# BattleBits_V3_partlyRouted.net
KiCad netlist of a schematic drawn in EAGLE
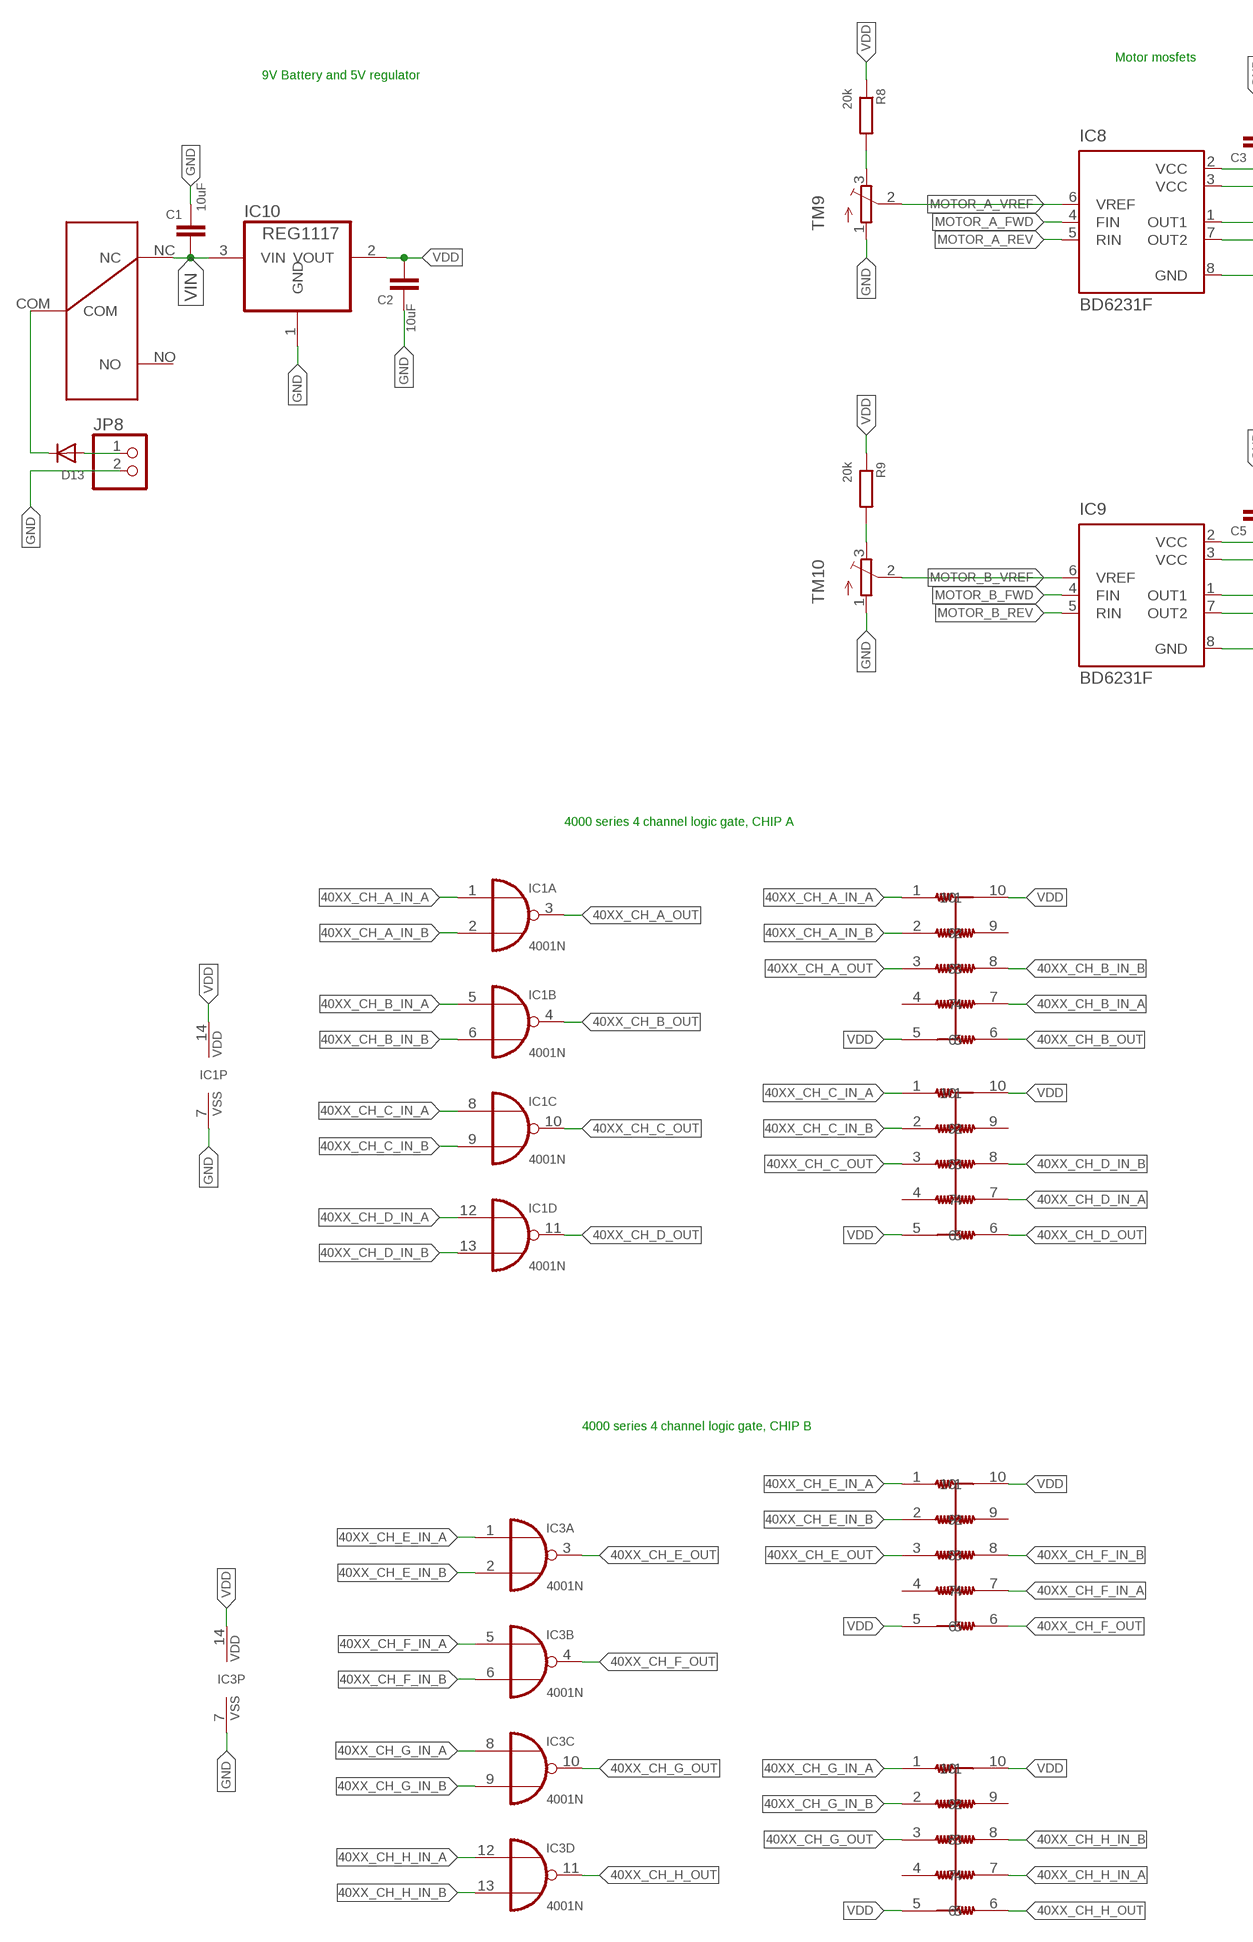
[diagram p0: schematic, sheet 1, part 1 of 2]
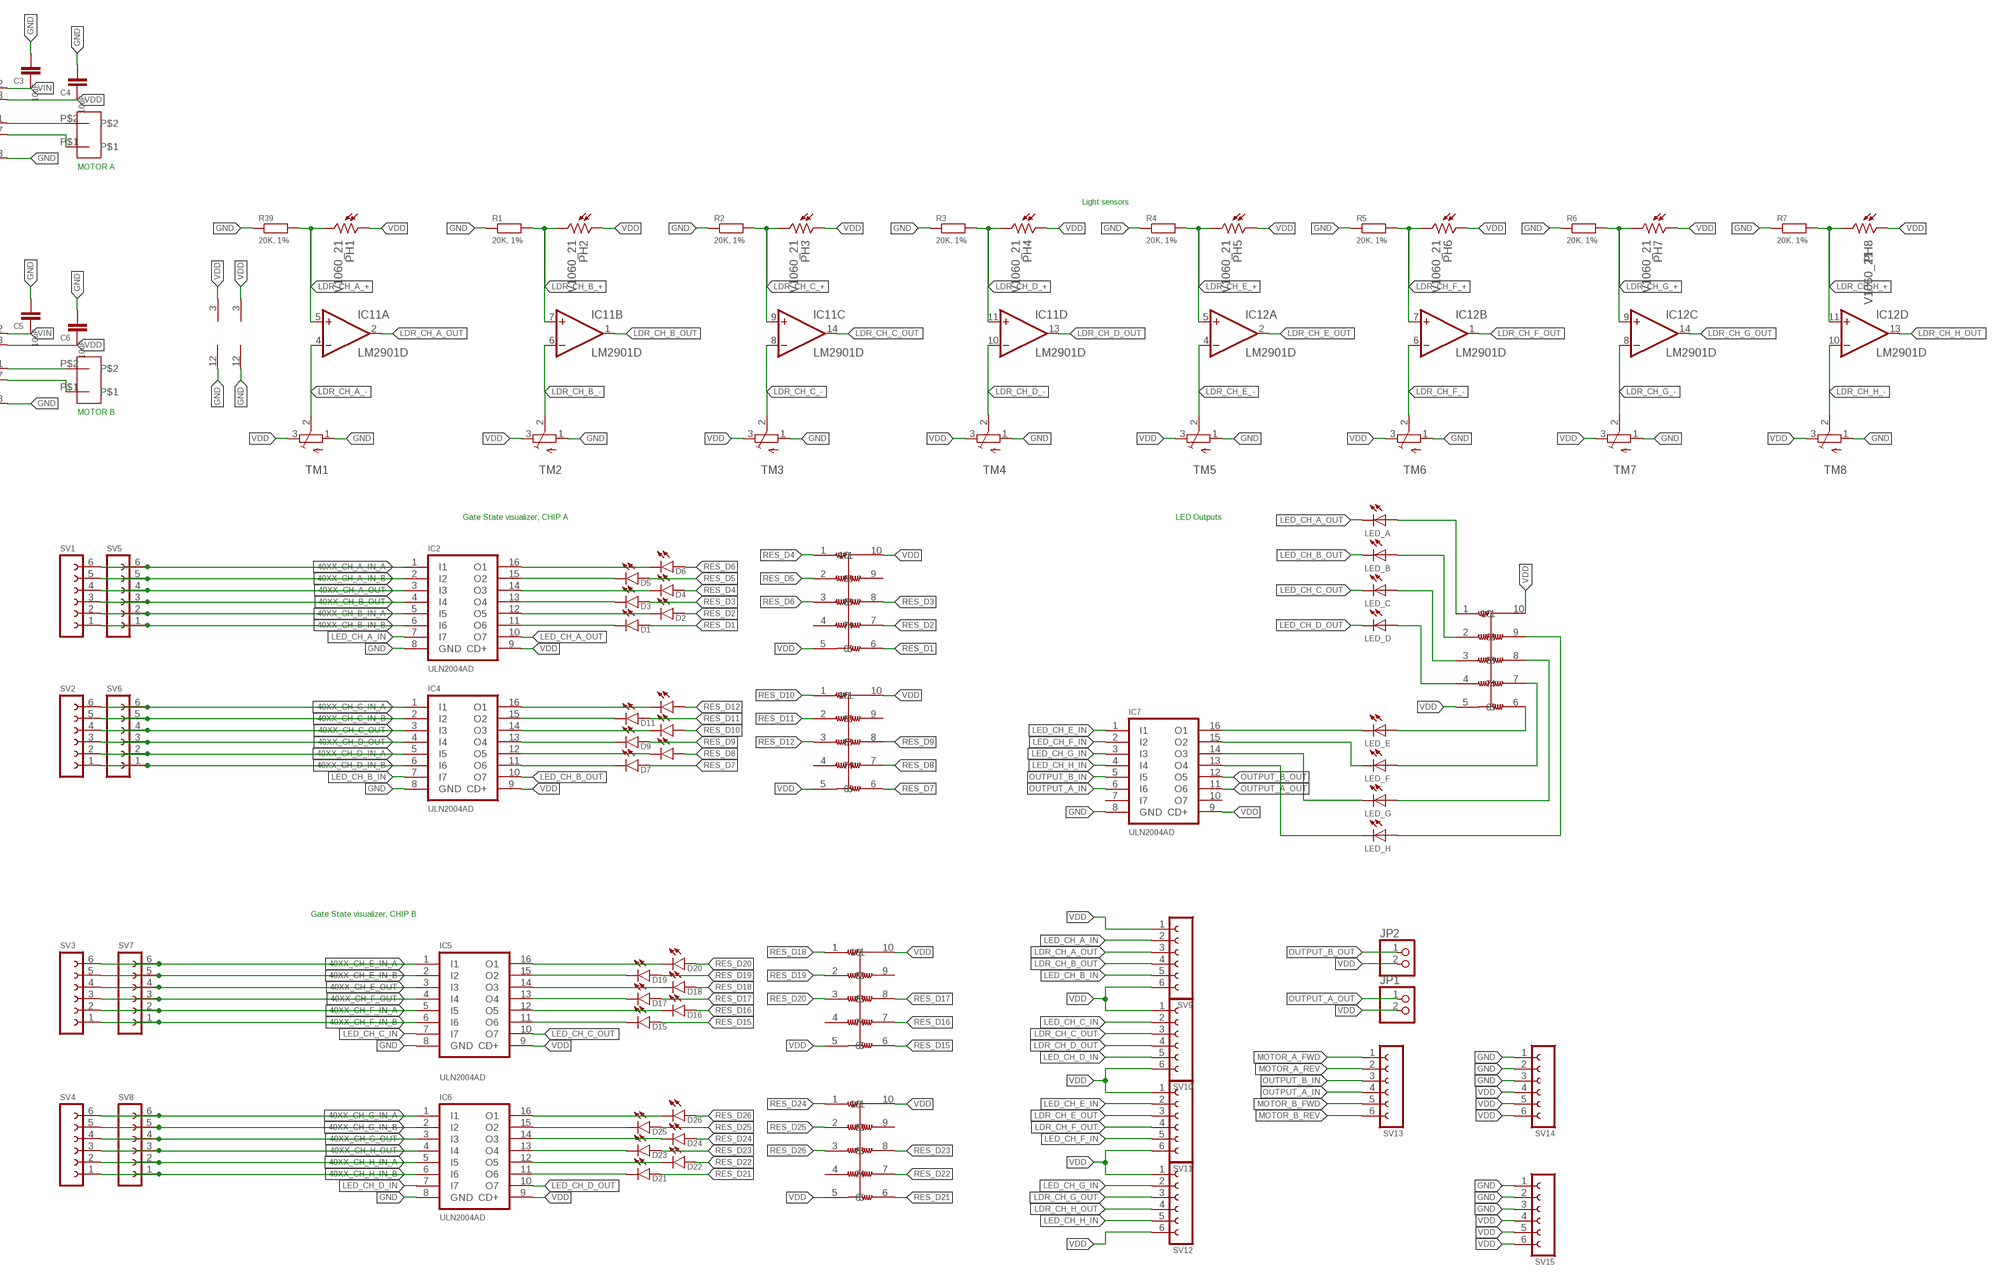
[diagram p1: schematic, sheet 1, part 2 of 2]

(export (version "E")
  (design (tool "Eeschema 10.0.6"))
  (components
    (comp (ref "C1")
      (value "10uF")
      (footprint "eagle-import:C3216")
      (libsource (lib "eagle-import") (part "C-EUC3216"))
    )
    (comp (ref "C2")
      (value "10uF")
      (footprint "eagle-import:C3216")
      (libsource (lib "eagle-import") (part "C-EUC3216"))
    )
    (comp (ref "C3")
      (value "10uF")
      (footprint "eagle-import:C3216")
      (libsource (lib "eagle-import") (part "C-EUC3216"))
    )
    (comp (ref "C4")
      (value "10uF")
      (footprint "eagle-import:C3216")
      (libsource (lib "eagle-import") (part "C-EUC3216"))
    )
    (comp (ref "C5")
      (value "10uF")
      (footprint "eagle-import:C3216")
      (libsource (lib "eagle-import") (part "C-EUC3216"))
    )
    (comp (ref "C6")
      (value "10uF")
      (footprint "eagle-import:C3216")
      (libsource (lib "eagle-import") (part "C-EUC3216"))
    )
    (comp (ref "D1")
      (value "LED1206")
      (footprint "eagle-import:LED-1206")
      (libsource (lib "eagle-import") (part "LED1206"))
    )
    (comp (ref "D2")
      (value "LED1206")
      (footprint "eagle-import:LED-1206")
      (libsource (lib "eagle-import") (part "LED1206"))
    )
    (comp (ref "D3")
      (value "LED1206")
      (footprint "eagle-import:LED-1206")
      (libsource (lib "eagle-import") (part "LED1206"))
    )
    (comp (ref "D4")
      (value "LED1206")
      (footprint "eagle-import:LED-1206")
      (libsource (lib "eagle-import") (part "LED1206"))
    )
    (comp (ref "D5")
      (value "LED1206")
      (footprint "eagle-import:LED-1206")
      (libsource (lib "eagle-import") (part "LED1206"))
    )
    (comp (ref "D6")
      (value "LED1206")
      (footprint "eagle-import:LED-1206")
      (libsource (lib "eagle-import") (part "LED1206"))
    )
    (comp (ref "D7")
      (value "LED1206")
      (footprint "eagle-import:LED-1206")
      (libsource (lib "eagle-import") (part "LED1206"))
    )
    (comp (ref "D8")
      (value "LED1206")
      (footprint "eagle-import:LED-1206")
      (libsource (lib "eagle-import") (part "LED1206"))
    )
    (comp (ref "D9")
      (value "LED1206")
      (footprint "eagle-import:LED-1206")
      (libsource (lib "eagle-import") (part "LED1206"))
    )
    (comp (ref "D10")
      (value "LED1206")
      (footprint "eagle-import:LED-1206")
      (libsource (lib "eagle-import") (part "LED1206"))
    )
    (comp (ref "D11")
      (value "LED1206")
      (footprint "eagle-import:LED-1206")
      (libsource (lib "eagle-import") (part "LED1206"))
    )
    (comp (ref "D12")
      (value "LED1206")
      (footprint "eagle-import:LED-1206")
      (libsource (lib "eagle-import") (part "LED1206"))
    )
    (comp (ref "D13")
      (value "DIODESMA")
      (footprint "eagle-import:SMADIODE")
      (libsource (lib "eagle-import") (part "DIODESMA"))
    )
    (comp (ref "D15")
      (value "LED1206")
      (footprint "eagle-import:LED-1206")
      (libsource (lib "eagle-import") (part "LED1206"))
    )
    (comp (ref "D16")
      (value "LED1206")
      (footprint "eagle-import:LED-1206")
      (libsource (lib "eagle-import") (part "LED1206"))
    )
    (comp (ref "D17")
      (value "LED1206")
      (footprint "eagle-import:LED-1206")
      (libsource (lib "eagle-import") (part "LED1206"))
    )
    (comp (ref "D18")
      (value "LED1206")
      (footprint "eagle-import:LED-1206")
      (libsource (lib "eagle-import") (part "LED1206"))
    )
    (comp (ref "D19")
      (value "LED1206")
      (footprint "eagle-import:LED-1206")
      (libsource (lib "eagle-import") (part "LED1206"))
    )
    (comp (ref "D20")
      (value "LED1206")
      (footprint "eagle-import:LED-1206")
      (libsource (lib "eagle-import") (part "LED1206"))
    )
    (comp (ref "D21")
      (value "LED1206")
      (footprint "eagle-import:LED-1206")
      (libsource (lib "eagle-import") (part "LED1206"))
    )
    (comp (ref "D22")
      (value "LED1206")
      (footprint "eagle-import:LED-1206")
      (libsource (lib "eagle-import") (part "LED1206"))
    )
    (comp (ref "D23")
      (value "LED1206")
      (footprint "eagle-import:LED-1206")
      (libsource (lib "eagle-import") (part "LED1206"))
    )
    (comp (ref "D24")
      (value "LED1206")
      (footprint "eagle-import:LED-1206")
      (libsource (lib "eagle-import") (part "LED1206"))
    )
    (comp (ref "D25")
      (value "LED1206")
      (footprint "eagle-import:LED-1206")
      (libsource (lib "eagle-import") (part "LED1206"))
    )
    (comp (ref "D26")
      (value "LED1206")
      (footprint "eagle-import:LED-1206")
      (libsource (lib "eagle-import") (part "LED1206"))
    )
    (comp (ref "IC1")
      (value "4001N")
      (footprint "eagle-import:DIL14")
      (libsource (lib "eagle-import") (part "4001N"))
    )
    (comp (ref "IC2")
      (value "ULN2004AD")
      (footprint "eagle-import:SO16")
      (libsource (lib "eagle-import") (part "ULN2004AD"))
    )
    (comp (ref "IC3")
      (value "4001N")
      (footprint "eagle-import:DIL14")
      (libsource (lib "eagle-import") (part "4001N"))
    )
    (comp (ref "IC4")
      (value "ULN2004AD")
      (footprint "eagle-import:SO16")
      (libsource (lib "eagle-import") (part "ULN2004AD"))
    )
    (comp (ref "IC5")
      (value "ULN2004AD")
      (footprint "eagle-import:SO16")
      (libsource (lib "eagle-import") (part "ULN2004AD"))
    )
    (comp (ref "IC6")
      (value "ULN2004AD")
      (footprint "eagle-import:SO16")
      (libsource (lib "eagle-import") (part "ULN2004AD"))
    )
    (comp (ref "IC7")
      (value "ULN2004AD")
      (footprint "eagle-import:SO16")
      (libsource (lib "eagle-import") (part "ULN2004AD"))
    )
    (comp (ref "IC8")
      (value "BD6231F")
      (footprint "eagle-import:SOP8")
      (fields (field (name "MPN") "BD6231F-E2"))
      (libsource (lib "eagle-import") (part "BD623F1"))
    )
    (comp (ref "IC9")
      (value "BD6231F")
      (footprint "eagle-import:SOP8")
      (fields (field (name "MPN") "BD6231F-E2"))
      (libsource (lib "eagle-import") (part "BD623F1"))
    )
    (comp (ref "IC10")
      (value "REG1117")
      (footprint "eagle-import:SOT223")
      (libsource (lib "eagle-import") (part "REG1117"))
    )
    (comp (ref "IC11")
      (value "LM2901D")
      (footprint "eagle-import:SO14")
      (libsource (lib "eagle-import") (part "LM2901D"))
    )
    (comp (ref "IC12")
      (value "LM2901D")
      (footprint "eagle-import:SO14")
      (libsource (lib "eagle-import") (part "LM2901D"))
    )
    (comp (ref "JP1")
      (value "PINHD-1X2")
      (footprint "eagle-import:1X02")
      (libsource (lib "eagle-import") (part "PINHD-1X2"))
    )
    (comp (ref "JP2")
      (value "PINHD-1X2")
      (footprint "eagle-import:1X02")
      (libsource (lib "eagle-import") (part "PINHD-1X2"))
    )
    (comp (ref "JP8")
      (value "PINHD-1X2")
      (footprint "eagle-import:1X02")
      (libsource (lib "eagle-import") (part "PINHD-1X2"))
    )
    (comp (ref "LED_A")
      (value "LED5MM")
      (footprint "eagle-import:LED5MM")
      (libsource (lib "eagle-import") (part "adafruit_420_LED5MM"))
    )
    (comp (ref "LED_B")
      (value "LED5MM")
      (footprint "eagle-import:LED5MM")
      (libsource (lib "eagle-import") (part "adafruit_420_LED5MM"))
    )
    (comp (ref "LED_C")
      (value "LED5MM")
      (footprint "eagle-import:LED5MM")
      (libsource (lib "eagle-import") (part "adafruit_420_LED5MM"))
    )
    (comp (ref "LED_D")
      (value "LED5MM")
      (footprint "eagle-import:LED5MM")
      (libsource (lib "eagle-import") (part "adafruit_420_LED5MM"))
    )
    (comp (ref "LED_E")
      (value "LED5MM")
      (footprint "eagle-import:LED5MM")
      (libsource (lib "eagle-import") (part "adafruit_420_LED5MM"))
    )
    (comp (ref "LED_F")
      (value "LED5MM")
      (footprint "eagle-import:LED5MM")
      (libsource (lib "eagle-import") (part "adafruit_420_LED5MM"))
    )
    (comp (ref "LED_G")
      (value "LED5MM")
      (footprint "eagle-import:LED5MM")
      (libsource (lib "eagle-import") (part "adafruit_420_LED5MM"))
    )
    (comp (ref "LED_H")
      (value "LED5MM")
      (footprint "eagle-import:LED5MM")
      (libsource (lib "eagle-import") (part "adafruit_420_LED5MM"))
    )
    (comp (ref "PH1")
      (value "V1060_21")
      (footprint "eagle-import:TO-5_V10")
      (libsource (lib "eagle-import") (part "?1060V_21"))
    )
    (comp (ref "PH2")
      (value "V1060_21")
      (footprint "eagle-import:TO-5_V10")
      (libsource (lib "eagle-import") (part "?1060V_21"))
    )
    (comp (ref "PH3")
      (value "V1060_21")
      (footprint "eagle-import:TO-5_V10")
      (libsource (lib "eagle-import") (part "?1060V_21"))
    )
    (comp (ref "PH4")
      (value "V1060_21")
      (footprint "eagle-import:TO-5_V10")
      (libsource (lib "eagle-import") (part "?1060V_21"))
    )
    (comp (ref "PH5")
      (value "V1060_21")
      (footprint "eagle-import:TO-5_V10")
      (libsource (lib "eagle-import") (part "?1060V_21"))
    )
    (comp (ref "PH6")
      (value "V1060_21")
      (footprint "eagle-import:TO-5_V10")
      (libsource (lib "eagle-import") (part "?1060V_21"))
    )
    (comp (ref "PH7")
      (value "V1060_21")
      (footprint "eagle-import:TO-5_V10")
      (libsource (lib "eagle-import") (part "?1060V_21"))
    )
    (comp (ref "PH8")
      (value "V1060_21")
      (footprint "eagle-import:TO-5_V10")
      (libsource (lib "eagle-import") (part "?1060V_21"))
    )
    (comp (ref "R1")
      (value "20K, 1%")
      (footprint "eagle-import:R3216")
      (libsource (lib "eagle-import") (part "R-EU_R3216"))
    )
    (comp (ref "R2")
      (value "20K, 1%")
      (footprint "eagle-import:R3216")
      (libsource (lib "eagle-import") (part "R-EU_R3216"))
    )
    (comp (ref "R3")
      (value "20K, 1%")
      (footprint "eagle-import:R3216")
      (libsource (lib "eagle-import") (part "R-EU_R3216"))
    )
    (comp (ref "R4")
      (value "20K, 1%")
      (footprint "eagle-import:R3216")
      (libsource (lib "eagle-import") (part "R-EU_R3216"))
    )
    (comp (ref "R5")
      (value "20K, 1%")
      (footprint "eagle-import:R3216")
      (libsource (lib "eagle-import") (part "R-EU_R3216"))
    )
    (comp (ref "R6")
      (value "20K, 1%")
      (footprint "eagle-import:R3216")
      (libsource (lib "eagle-import") (part "R-EU_R3216"))
    )
    (comp (ref "R7")
      (value "20K, 1%")
      (footprint "eagle-import:R3216")
      (libsource (lib "eagle-import") (part "R-EU_R3216"))
    )
    (comp (ref "R8")
      (value "20k")
      (footprint "eagle-import:R3216")
      (libsource (lib "eagle-import") (part "R-EU_R3216"))
    )
    (comp (ref "R9")
      (value "20k")
      (footprint "eagle-import:R3216")
      (libsource (lib "eagle-import") (part "R-EU_R3216"))
    )
    (comp (ref "R39")
      (value "20K, 1%")
      (footprint "eagle-import:R3216")
      (libsource (lib "eagle-import") (part "R-EU_R3216"))
    )
    (comp (ref "SV1")
      (value "FE06-1")
      (footprint "eagle-import:FE06")
      (libsource (lib "eagle-import") (part "FE06-1"))
    )
    (comp (ref "SV2")
      (value "FE06-1")
      (footprint "eagle-import:FE06")
      (libsource (lib "eagle-import") (part "FE06-1"))
    )
    (comp (ref "SV3")
      (value "FE06-1")
      (footprint "eagle-import:FE06")
      (libsource (lib "eagle-import") (part "FE06-1"))
    )
    (comp (ref "SV4")
      (value "FE06-1")
      (footprint "eagle-import:FE06")
      (libsource (lib "eagle-import") (part "FE06-1"))
    )
    (comp (ref "SV5")
      (value "FE06-1")
      (footprint "eagle-import:FE06")
      (libsource (lib "eagle-import") (part "FE06-1"))
    )
    (comp (ref "SV6")
      (value "FE06-1")
      (footprint "eagle-import:FE06")
      (libsource (lib "eagle-import") (part "FE06-1"))
    )
    (comp (ref "SV7")
      (value "FE06-1")
      (footprint "eagle-import:FE06")
      (libsource (lib "eagle-import") (part "FE06-1"))
    )
    (comp (ref "SV8")
      (value "FE06-1")
      (footprint "eagle-import:FE06")
      (libsource (lib "eagle-import") (part "FE06-1"))
    )
    (comp (ref "SV9")
      (value "FE06-1")
      (footprint "eagle-import:FE06")
      (libsource (lib "eagle-import") (part "FE06-1"))
    )
    (comp (ref "SV10")
      (value "FE06-1")
      (footprint "eagle-import:FE06")
      (libsource (lib "eagle-import") (part "FE06-1"))
    )
    (comp (ref "SV11")
      (value "FE06-1")
      (footprint "eagle-import:FE06")
      (libsource (lib "eagle-import") (part "FE06-1"))
    )
    (comp (ref "SV12")
      (value "FE06-1")
      (footprint "eagle-import:FE06")
      (libsource (lib "eagle-import") (part "FE06-1"))
    )
    (comp (ref "SV13")
      (value "FE06-1")
      (footprint "eagle-import:FE06")
      (libsource (lib "eagle-import") (part "FE06-1"))
    )
    (comp (ref "SV14")
      (value "FE06-1")
      (footprint "eagle-import:FE06")
      (libsource (lib "eagle-import") (part "FE06-1"))
    )
    (comp (ref "SV15")
      (value "FE06-1")
      (footprint "eagle-import:FE06")
      (libsource (lib "eagle-import") (part "FE06-1"))
    )
    (comp (ref "TM1")
      (value "TRIMPOTTC33X")
      (footprint "eagle-import:TC33X")
      (libsource (lib "eagle-import") (part "TRIMPOTTC33X"))
    )
    (comp (ref "TM2")
      (value "TRIMPOTTC33X")
      (footprint "eagle-import:TC33X")
      (libsource (lib "eagle-import") (part "TRIMPOTTC33X"))
    )
    (comp (ref "TM3")
      (value "TRIMPOTTC33X")
      (footprint "eagle-import:TC33X")
      (libsource (lib "eagle-import") (part "TRIMPOTTC33X"))
    )
    (comp (ref "TM4")
      (value "TRIMPOTTC33X")
      (footprint "eagle-import:TC33X")
      (libsource (lib "eagle-import") (part "TRIMPOTTC33X"))
    )
    (comp (ref "TM5")
      (value "TRIMPOTTC33X")
      (footprint "eagle-import:TC33X")
      (libsource (lib "eagle-import") (part "TRIMPOTTC33X"))
    )
    (comp (ref "TM6")
      (value "TRIMPOTTC33X")
      (footprint "eagle-import:TC33X")
      (libsource (lib "eagle-import") (part "TRIMPOTTC33X"))
    )
    (comp (ref "TM7")
      (value "TRIMPOTTC33X")
      (footprint "eagle-import:TC33X")
      (libsource (lib "eagle-import") (part "TRIMPOTTC33X"))
    )
    (comp (ref "TM8")
      (value "TRIMPOTTC33X")
      (footprint "eagle-import:TC33X")
      (libsource (lib "eagle-import") (part "TRIMPOTTC33X"))
    )
    (comp (ref "TM9")
      (value "TRIMPOTTC33X")
      (footprint "eagle-import:TC33X")
      (libsource (lib "eagle-import") (part "TRIMPOTTC33X"))
    )
    (comp (ref "TM10")
      (value "TRIMPOTTC33X")
      (footprint "eagle-import:TC33X")
      (libsource (lib "eagle-import") (part "TRIMPOTTC33X"))
    )
    (comp (ref "U$1")
      (value "MOTOR")
      (footprint "eagle-import:GEARMOTOR")
      (libsource (lib "eagle-import") (part "MOTOR"))
    )
    (comp (ref "U$2")
      (value "MOTOR")
      (footprint "eagle-import:GEARMOTOR")
      (libsource (lib "eagle-import") (part "MOTOR"))
    )
    (comp (ref "U$3")
      (value "10K")
      (footprint "eagle-import:EXBA")
      (libsource (lib "eagle-import") (part "EXBA_10P"))
    )
    (comp (ref "U$4")
      (value "330")
      (footprint "eagle-import:EXBA")
      (libsource (lib "eagle-import") (part "EXBA_10P"))
    )
    (comp (ref "U$5")
      (value "10K")
      (footprint "eagle-import:EXBA")
      (libsource (lib "eagle-import") (part "EXBA_10P"))
    )
    (comp (ref "U$6")
      (value "10K")
      (footprint "eagle-import:EXBA")
      (libsource (lib "eagle-import") (part "EXBA_10P"))
    )
    (comp (ref "U$7")
      (value "SLIDE_SWITCH")
      (footprint "eagle-import:SLIDE_SWITCH")
      (libsource (lib "eagle-import") (part "SLIDE_SWITCH"))
    )
    (comp (ref "U$9")
      (value "10K")
      (footprint "eagle-import:EXBA")
      (libsource (lib "eagle-import") (part "EXBA_10P"))
    )
    (comp (ref "U$10")
      (value "10K")
      (footprint "eagle-import:EXBA")
      (libsource (lib "eagle-import") (part "EXBA_10P"))
    )
    (comp (ref "U$11")
      (value "10K")
      (footprint "eagle-import:EXBA")
      (libsource (lib "eagle-import") (part "EXBA_10P"))
    )
    (comp (ref "U$19")
      (value "10K")
      (footprint "eagle-import:EXBA")
      (libsource (lib "eagle-import") (part "EXBA_10P"))
    )
    (comp (ref "U$20")
      (value "10K")
      (footprint "eagle-import:EXBA")
      (libsource (lib "eagle-import") (part "EXBA_10P"))
    )
  )
  (nets
    (net (code "1") (name "40XX_CH_A_IN_A") (class "Default")
      (node (ref "IC1") (pin "1") (pinfunction "I0_1") (pintype "input"))
      (node (ref "IC2") (pin "1") (pinfunction "I1_1") (pintype "input"))
      (node (ref "SV1") (pin "6") (pinfunction "6_6") (pintype "passive"))
      (node (ref "SV5") (pin "6") (pinfunction "6_6") (pintype "passive"))
      (node (ref "U$3") (pin "1") (pinfunction "1_1") (pintype "bidirectional"))
    )
    (net (code "2") (name "40XX_CH_A_IN_B") (class "Default")
      (node (ref "IC1") (pin "2") (pinfunction "I1_2") (pintype "input"))
      (node (ref "IC2") (pin "2") (pinfunction "I2_2") (pintype "input"))
      (node (ref "SV1") (pin "5") (pinfunction "5_5") (pintype "passive"))
      (node (ref "SV5") (pin "5") (pinfunction "5_5") (pintype "passive"))
      (node (ref "U$3") (pin "2") (pinfunction "2_2") (pintype "bidirectional"))
    )
    (net (code "3") (name "40XX_CH_A_OUT") (class "Default")
      (node (ref "IC1") (pin "3") (pinfunction "O_3") (pintype "output"))
      (node (ref "IC2") (pin "3") (pinfunction "I3_3") (pintype "input"))
      (node (ref "SV1") (pin "4") (pinfunction "4_4") (pintype "passive"))
      (node (ref "SV5") (pin "4") (pinfunction "4_4") (pintype "passive"))
      (node (ref "U$3") (pin "3") (pinfunction "3_3") (pintype "bidirectional"))
    )
    (net (code "4") (name "40XX_CH_B_IN_A") (class "Default")
      (node (ref "IC1") (pin "5") (pinfunction "I0_5") (pintype "input"))
      (node (ref "IC2") (pin "5") (pinfunction "I5_5") (pintype "input"))
      (node (ref "SV1") (pin "2") (pinfunction "2_2") (pintype "passive"))
      (node (ref "SV5") (pin "2") (pinfunction "2_2") (pintype "passive"))
      (node (ref "U$3") (pin "7") (pinfunction "7_7") (pintype "bidirectional"))
    )
    (net (code "5") (name "40XX_CH_B_IN_B") (class "Default")
      (node (ref "IC1") (pin "6") (pinfunction "I1_6") (pintype "input"))
      (node (ref "IC2") (pin "6") (pinfunction "I6_6") (pintype "input"))
      (node (ref "SV1") (pin "1") (pinfunction "1_1") (pintype "passive"))
      (node (ref "SV5") (pin "1") (pinfunction "1_1") (pintype "passive"))
      (node (ref "U$3") (pin "8") (pinfunction "8_8") (pintype "bidirectional"))
    )
    (net (code "6") (name "40XX_CH_B_OUT") (class "Default")
      (node (ref "IC1") (pin "4") (pinfunction "O_4") (pintype "output"))
      (node (ref "IC2") (pin "4") (pinfunction "I4_4") (pintype "input"))
      (node (ref "SV1") (pin "3") (pinfunction "3_3") (pintype "passive"))
      (node (ref "SV5") (pin "3") (pinfunction "3_3") (pintype "passive"))
      (node (ref "U$3") (pin "6") (pinfunction "6_6") (pintype "bidirectional"))
    )
    (net (code "7") (name "40XX_CH_C_IN_A") (class "Default")
      (node (ref "IC1") (pin "8") (pinfunction "I0_8") (pintype "input"))
      (node (ref "IC4") (pin "1") (pinfunction "I1_1") (pintype "input"))
      (node (ref "SV2") (pin "6") (pinfunction "6_6") (pintype "passive"))
      (node (ref "SV6") (pin "6") (pinfunction "6_6") (pintype "passive"))
      (node (ref "U$10") (pin "1") (pinfunction "1_1") (pintype "bidirectional"))
    )
    (net (code "8") (name "40XX_CH_C_IN_B") (class "Default")
      (node (ref "IC1") (pin "9") (pinfunction "I1_9") (pintype "input"))
      (node (ref "IC4") (pin "2") (pinfunction "I2_2") (pintype "input"))
      (node (ref "SV2") (pin "5") (pinfunction "5_5") (pintype "passive"))
      (node (ref "SV6") (pin "5") (pinfunction "5_5") (pintype "passive"))
      (node (ref "U$10") (pin "2") (pinfunction "2_2") (pintype "bidirectional"))
    )
    (net (code "9") (name "40XX_CH_C_OUT") (class "Default")
      (node (ref "IC1") (pin "10") (pinfunction "O_10") (pintype "output"))
      (node (ref "IC4") (pin "3") (pinfunction "I3_3") (pintype "input"))
      (node (ref "SV2") (pin "4") (pinfunction "4_4") (pintype "passive"))
      (node (ref "SV6") (pin "4") (pinfunction "4_4") (pintype "passive"))
      (node (ref "U$10") (pin "3") (pinfunction "3_3") (pintype "bidirectional"))
    )
    (net (code "10") (name "40XX_CH_D_IN_A") (class "Default")
      (node (ref "IC1") (pin "12") (pinfunction "I0_12") (pintype "input"))
      (node (ref "IC4") (pin "5") (pinfunction "I5_5") (pintype "input"))
      (node (ref "SV2") (pin "2") (pinfunction "2_2") (pintype "passive"))
      (node (ref "SV6") (pin "2") (pinfunction "2_2") (pintype "passive"))
      (node (ref "U$10") (pin "7") (pinfunction "7_7") (pintype "bidirectional"))
    )
    (net (code "11") (name "40XX_CH_D_IN_B") (class "Default")
      (node (ref "IC1") (pin "13") (pinfunction "I1_13") (pintype "input"))
      (node (ref "IC4") (pin "6") (pinfunction "I6_6") (pintype "input"))
      (node (ref "SV2") (pin "1") (pinfunction "1_1") (pintype "passive"))
      (node (ref "SV6") (pin "1") (pinfunction "1_1") (pintype "passive"))
      (node (ref "U$10") (pin "8") (pinfunction "8_8") (pintype "bidirectional"))
    )
    (net (code "12") (name "40XX_CH_D_OUT") (class "Default")
      (node (ref "IC1") (pin "11") (pinfunction "O_11") (pintype "output"))
      (node (ref "IC4") (pin "4") (pinfunction "I4_4") (pintype "input"))
      (node (ref "SV2") (pin "3") (pinfunction "3_3") (pintype "passive"))
      (node (ref "SV6") (pin "3") (pinfunction "3_3") (pintype "passive"))
      (node (ref "U$10") (pin "6") (pinfunction "6_6") (pintype "bidirectional"))
    )
    (net (code "13") (name "40XX_CH_E_IN_A") (class "Default")
      (node (ref "IC3") (pin "1") (pinfunction "I0_1") (pintype "input"))
      (node (ref "IC5") (pin "1") (pinfunction "I1_1") (pintype "input"))
      (node (ref "SV3") (pin "6") (pinfunction "6_6") (pintype "passive"))
      (node (ref "SV7") (pin "6") (pinfunction "6_6") (pintype "passive"))
      (node (ref "U$11") (pin "1") (pinfunction "1_1") (pintype "bidirectional"))
    )
    (net (code "14") (name "40XX_CH_E_IN_B") (class "Default")
      (node (ref "IC3") (pin "2") (pinfunction "I1_2") (pintype "input"))
      (node (ref "IC5") (pin "2") (pinfunction "I2_2") (pintype "input"))
      (node (ref "SV3") (pin "5") (pinfunction "5_5") (pintype "passive"))
      (node (ref "SV7") (pin "5") (pinfunction "5_5") (pintype "passive"))
      (node (ref "U$11") (pin "2") (pinfunction "2_2") (pintype "bidirectional"))
    )
    (net (code "15") (name "40XX_CH_E_OUT") (class "Default")
      (node (ref "IC3") (pin "3") (pinfunction "O_3") (pintype "output"))
      (node (ref "IC5") (pin "3") (pinfunction "I3_3") (pintype "input"))
      (node (ref "SV3") (pin "4") (pinfunction "4_4") (pintype "passive"))
      (node (ref "SV7") (pin "4") (pinfunction "4_4") (pintype "passive"))
      (node (ref "U$11") (pin "3") (pinfunction "3_3") (pintype "bidirectional"))
    )
    (net (code "16") (name "40XX_CH_F_IN_A") (class "Default")
      (node (ref "IC3") (pin "5") (pinfunction "I0_5") (pintype "input"))
      (node (ref "IC5") (pin "5") (pinfunction "I5_5") (pintype "input"))
      (node (ref "SV3") (pin "2") (pinfunction "2_2") (pintype "passive"))
      (node (ref "SV7") (pin "2") (pinfunction "2_2") (pintype "passive"))
      (node (ref "U$11") (pin "7") (pinfunction "7_7") (pintype "bidirectional"))
    )
    (net (code "17") (name "40XX_CH_F_IN_B") (class "Default")
      (node (ref "IC3") (pin "6") (pinfunction "I1_6") (pintype "input"))
      (node (ref "IC5") (pin "6") (pinfunction "I6_6") (pintype "input"))
      (node (ref "SV3") (pin "1") (pinfunction "1_1") (pintype "passive"))
      (node (ref "SV7") (pin "1") (pinfunction "1_1") (pintype "passive"))
      (node (ref "U$11") (pin "8") (pinfunction "8_8") (pintype "bidirectional"))
    )
    (net (code "18") (name "40XX_CH_F_OUT") (class "Default")
      (node (ref "IC3") (pin "4") (pinfunction "O_4") (pintype "output"))
      (node (ref "IC5") (pin "4") (pinfunction "I4_4") (pintype "input"))
      (node (ref "SV3") (pin "3") (pinfunction "3_3") (pintype "passive"))
      (node (ref "SV7") (pin "3") (pinfunction "3_3") (pintype "passive"))
      (node (ref "U$11") (pin "6") (pinfunction "6_6") (pintype "bidirectional"))
    )
    (net (code "19") (name "40XX_CH_G_IN_A") (class "Default")
      (node (ref "IC3") (pin "8") (pinfunction "I0_8") (pintype "input"))
      (node (ref "IC6") (pin "1") (pinfunction "I1_1") (pintype "input"))
      (node (ref "SV4") (pin "6") (pinfunction "6_6") (pintype "passive"))
      (node (ref "SV8") (pin "6") (pinfunction "6_6") (pintype "passive"))
      (node (ref "U$20") (pin "1") (pinfunction "1_1") (pintype "bidirectional"))
    )
    (net (code "20") (name "40XX_CH_G_IN_B") (class "Default")
      (node (ref "IC3") (pin "9") (pinfunction "I1_9") (pintype "input"))
      (node (ref "IC6") (pin "2") (pinfunction "I2_2") (pintype "input"))
      (node (ref "SV4") (pin "5") (pinfunction "5_5") (pintype "passive"))
      (node (ref "SV8") (pin "5") (pinfunction "5_5") (pintype "passive"))
      (node (ref "U$20") (pin "2") (pinfunction "2_2") (pintype "bidirectional"))
    )
    (net (code "21") (name "40XX_CH_G_OUT") (class "Default")
      (node (ref "IC3") (pin "10") (pinfunction "O_10") (pintype "output"))
      (node (ref "IC6") (pin "3") (pinfunction "I3_3") (pintype "input"))
      (node (ref "SV4") (pin "4") (pinfunction "4_4") (pintype "passive"))
      (node (ref "SV8") (pin "4") (pinfunction "4_4") (pintype "passive"))
      (node (ref "U$20") (pin "3") (pinfunction "3_3") (pintype "bidirectional"))
    )
    (net (code "22") (name "40XX_CH_H_IN_A") (class "Default")
      (node (ref "IC3") (pin "12") (pinfunction "I0_12") (pintype "input"))
      (node (ref "IC6") (pin "5") (pinfunction "I5_5") (pintype "input"))
      (node (ref "SV4") (pin "2") (pinfunction "2_2") (pintype "passive"))
      (node (ref "SV8") (pin "2") (pinfunction "2_2") (pintype "passive"))
      (node (ref "U$20") (pin "7") (pinfunction "7_7") (pintype "bidirectional"))
    )
    (net (code "23") (name "40XX_CH_H_IN_B") (class "Default")
      (node (ref "IC3") (pin "13") (pinfunction "I1_13") (pintype "input"))
      (node (ref "IC6") (pin "6") (pinfunction "I6_6") (pintype "input"))
      (node (ref "SV4") (pin "1") (pinfunction "1_1") (pintype "passive"))
      (node (ref "SV8") (pin "1") (pinfunction "1_1") (pintype "passive"))
      (node (ref "U$20") (pin "8") (pinfunction "8_8") (pintype "bidirectional"))
    )
    (net (code "24") (name "40XX_CH_H_OUT") (class "Default")
      (node (ref "IC3") (pin "11") (pinfunction "O_11") (pintype "output"))
      (node (ref "IC6") (pin "4") (pinfunction "I4_4") (pintype "input"))
      (node (ref "SV4") (pin "3") (pinfunction "3_3") (pintype "passive"))
      (node (ref "SV8") (pin "3") (pinfunction "3_3") (pintype "passive"))
      (node (ref "U$20") (pin "6") (pinfunction "6_6") (pintype "bidirectional"))
    )
    (net (code "25") (name "GND") (class "Default")
      (node (ref "C1") (pin "1") (pinfunction "1_1") (pintype "passive"))
      (node (ref "C2") (pin "1") (pinfunction "1_1") (pintype "passive"))
      (node (ref "C3") (pin "2") (pinfunction "2_2") (pintype "passive"))
      (node (ref "C4") (pin "2") (pinfunction "2_2") (pintype "passive"))
      (node (ref "C5") (pin "2") (pinfunction "2_2") (pintype "passive"))
      (node (ref "C6") (pin "2") (pinfunction "2_2") (pintype "passive"))
      (node (ref "IC1") (pin "7") (pinfunction "VSS_7") (pintype "power_in"))
      (node (ref "IC10") (pin "1") (pinfunction "GND_1") (pintype "power_in"))
      (node (ref "IC11") (pin "12") (pinfunction "V-_12") (pintype "power_in"))
      (node (ref "IC12") (pin "12") (pinfunction "V-_12") (pintype "power_in"))
      (node (ref "IC2") (pin "8") (pinfunction "GND_8") (pintype "power_in"))
      (node (ref "IC3") (pin "7") (pinfunction "VSS_7") (pintype "power_in"))
      (node (ref "IC4") (pin "8") (pinfunction "GND_8") (pintype "power_in"))
      (node (ref "IC5") (pin "8") (pinfunction "GND_8") (pintype "power_in"))
      (node (ref "IC6") (pin "8") (pinfunction "GND_8") (pintype "power_in"))
      (node (ref "IC7") (pin "8") (pinfunction "GND_8") (pintype "power_in"))
      (node (ref "IC8") (pin "8") (pinfunction "GND_8") (pintype "power_in"))
      (node (ref "IC9") (pin "8") (pinfunction "GND_8") (pintype "power_in"))
      (node (ref "JP8") (pin "2") (pinfunction "2_2") (pintype "passive"))
      (node (ref "R1") (pin "1") (pinfunction "1_1") (pintype "passive"))
      (node (ref "R2") (pin "1") (pinfunction "1_1") (pintype "passive"))
      (node (ref "R3") (pin "1") (pinfunction "1_1") (pintype "passive"))
      (node (ref "R39") (pin "1") (pinfunction "1_1") (pintype "passive"))
      (node (ref "R4") (pin "1") (pinfunction "1_1") (pintype "passive"))
      (node (ref "R5") (pin "1") (pinfunction "1_1") (pintype "passive"))
      (node (ref "R6") (pin "1") (pinfunction "1_1") (pintype "passive"))
      (node (ref "R7") (pin "1") (pinfunction "1_1") (pintype "passive"))
      (node (ref "SV14") (pin "1") (pinfunction "1_1") (pintype "passive"))
      (node (ref "SV14") (pin "2") (pinfunction "2_2") (pintype "passive"))
      (node (ref "SV14") (pin "3") (pinfunction "3_3") (pintype "passive"))
      (node (ref "SV15") (pin "1") (pinfunction "1_1") (pintype "passive"))
      (node (ref "SV15") (pin "2") (pinfunction "2_2") (pintype "passive"))
      (node (ref "SV15") (pin "3") (pinfunction "3_3") (pintype "passive"))
      (node (ref "TM1") (pin "1") (pinfunction "A_1") (pintype "passive"))
      (node (ref "TM10") (pin "1") (pinfunction "A_1") (pintype "passive"))
      (node (ref "TM2") (pin "1") (pinfunction "A_1") (pintype "passive"))
      (node (ref "TM3") (pin "1") (pinfunction "A_1") (pintype "passive"))
      (node (ref "TM4") (pin "1") (pinfunction "A_1") (pintype "passive"))
      (node (ref "TM5") (pin "1") (pinfunction "A_1") (pintype "passive"))
      (node (ref "TM6") (pin "1") (pinfunction "A_1") (pintype "passive"))
      (node (ref "TM7") (pin "1") (pinfunction "A_1") (pintype "passive"))
      (node (ref "TM8") (pin "1") (pinfunction "A_1") (pintype "passive"))
      (node (ref "TM9") (pin "1") (pinfunction "A_1") (pintype "passive"))
    )
    (net (code "26") (name "LDR_CH_A_+") (class "Default")
      (node (ref "IC11") (pin "5") (pinfunction "+IN_5") (pintype "input"))
      (node (ref "PH1") (pin "2") (pinfunction "2_2") (pintype "passive"))
      (node (ref "R39") (pin "2") (pinfunction "2_2") (pintype "passive"))
    )
    (net (code "27") (name "LDR_CH_A_-") (class "Default")
      (node (ref "IC11") (pin "4") (pinfunction "-IN_4") (pintype "input"))
      (node (ref "TM1") (pin "2") (pinfunction "S_2") (pintype "passive"))
    )
    (net (code "28") (name "LDR_CH_A_OUT") (class "Default")
      (node (ref "IC11") (pin "2") (pinfunction "OUT_2") (pintype "output"))
      (node (ref "SV9") (pin "3") (pinfunction "3_3") (pintype "passive"))
    )
    (net (code "29") (name "LDR_CH_B_+") (class "Default")
      (node (ref "IC11") (pin "7") (pinfunction "+IN_7") (pintype "input"))
      (node (ref "PH2") (pin "2") (pinfunction "2_2") (pintype "passive"))
      (node (ref "R1") (pin "2") (pinfunction "2_2") (pintype "passive"))
    )
    (net (code "30") (name "LDR_CH_B_-") (class "Default")
      (node (ref "IC11") (pin "6") (pinfunction "-IN_6") (pintype "input"))
      (node (ref "TM2") (pin "2") (pinfunction "S_2") (pintype "passive"))
    )
    (net (code "31") (name "LDR_CH_B_OUT") (class "Default")
      (node (ref "IC11") (pin "1") (pinfunction "OUT_1") (pintype "output"))
      (node (ref "SV9") (pin "4") (pinfunction "4_4") (pintype "passive"))
    )
    (net (code "32") (name "LDR_CH_C_+") (class "Default")
      (node (ref "IC11") (pin "9") (pinfunction "+IN_9") (pintype "input"))
      (node (ref "PH3") (pin "2") (pinfunction "2_2") (pintype "passive"))
      (node (ref "R2") (pin "2") (pinfunction "2_2") (pintype "passive"))
    )
    (net (code "33") (name "LDR_CH_C_-") (class "Default")
      (node (ref "IC11") (pin "8") (pinfunction "-IN_8") (pintype "input"))
      (node (ref "TM3") (pin "2") (pinfunction "S_2") (pintype "passive"))
    )
    (net (code "34") (name "LDR_CH_C_OUT") (class "Default")
      (node (ref "IC11") (pin "14") (pinfunction "OUT_14") (pintype "output"))
      (node (ref "SV10") (pin "3") (pinfunction "3_3") (pintype "passive"))
    )
    (net (code "35") (name "LDR_CH_D_+") (class "Default")
      (node (ref "IC11") (pin "11") (pinfunction "+IN_11") (pintype "input"))
      (node (ref "PH4") (pin "2") (pinfunction "2_2") (pintype "passive"))
      (node (ref "R3") (pin "2") (pinfunction "2_2") (pintype "passive"))
    )
    (net (code "36") (name "LDR_CH_D_-") (class "Default")
      (node (ref "IC11") (pin "10") (pinfunction "-IN_10") (pintype "input"))
      (node (ref "TM4") (pin "2") (pinfunction "S_2") (pintype "passive"))
    )
    (net (code "37") (name "LDR_CH_D_OUT") (class "Default")
      (node (ref "IC11") (pin "13") (pinfunction "OUT_13") (pintype "output"))
      (node (ref "SV10") (pin "4") (pinfunction "4_4") (pintype "passive"))
    )
    (net (code "38") (name "LDR_CH_E_+") (class "Default")
      (node (ref "IC12") (pin "5") (pinfunction "+IN_5") (pintype "input"))
      (node (ref "PH5") (pin "2") (pinfunction "2_2") (pintype "passive"))
      (node (ref "R4") (pin "2") (pinfunction "2_2") (pintype "passive"))
    )
    (net (code "39") (name "LDR_CH_E_-") (class "Default")
      (node (ref "IC12") (pin "4") (pinfunction "-IN_4") (pintype "input"))
      (node (ref "TM5") (pin "2") (pinfunction "S_2") (pintype "passive"))
    )
    (net (code "40") (name "LDR_CH_E_OUT") (class "Default")
      (node (ref "IC12") (pin "2") (pinfunction "OUT_2") (pintype "output"))
      (node (ref "SV11") (pin "3") (pinfunction "3_3") (pintype "passive"))
    )
    (net (code "41") (name "LDR_CH_F_+") (class "Default")
      (node (ref "IC12") (pin "7") (pinfunction "+IN_7") (pintype "input"))
      (node (ref "PH6") (pin "2") (pinfunction "2_2") (pintype "passive"))
      (node (ref "R5") (pin "2") (pinfunction "2_2") (pintype "passive"))
    )
    (net (code "42") (name "LDR_CH_F_-") (class "Default")
      (node (ref "IC12") (pin "6") (pinfunction "-IN_6") (pintype "input"))
      (node (ref "TM6") (pin "2") (pinfunction "S_2") (pintype "passive"))
    )
    (net (code "43") (name "LDR_CH_F_OUT") (class "Default")
      (node (ref "IC12") (pin "1") (pinfunction "OUT_1") (pintype "output"))
      (node (ref "SV11") (pin "4") (pinfunction "4_4") (pintype "passive"))
    )
    (net (code "44") (name "LDR_CH_G_+") (class "Default")
      (node (ref "IC12") (pin "9") (pinfunction "+IN_9") (pintype "input"))
      (node (ref "PH7") (pin "2") (pinfunction "2_2") (pintype "passive"))
      (node (ref "R6") (pin "2") (pinfunction "2_2") (pintype "passive"))
    )
    (net (code "45") (name "LDR_CH_G_-") (class "Default")
      (node (ref "IC12") (pin "8") (pinfunction "-IN_8") (pintype "input"))
      (node (ref "TM7") (pin "2") (pinfunction "S_2") (pintype "passive"))
    )
    (net (code "46") (name "LDR_CH_G_OUT") (class "Default")
      (node (ref "IC12") (pin "14") (pinfunction "OUT_14") (pintype "output"))
      (node (ref "SV12") (pin "3") (pinfunction "3_3") (pintype "passive"))
    )
    (net (code "47") (name "LDR_CH_H_+") (class "Default")
      (node (ref "IC12") (pin "11") (pinfunction "+IN_11") (pintype "input"))
      (node (ref "PH8") (pin "2") (pinfunction "2_2") (pintype "passive"))
      (node (ref "R7") (pin "2") (pinfunction "2_2") (pintype "passive"))
    )
    (net (code "48") (name "LDR_CH_H_-") (class "Default")
      (node (ref "IC12") (pin "10") (pinfunction "-IN_10") (pintype "input"))
      (node (ref "TM8") (pin "2") (pinfunction "S_2") (pintype "passive"))
    )
    (net (code "49") (name "LDR_CH_H_OUT") (class "Default")
      (node (ref "IC12") (pin "13") (pinfunction "OUT_13") (pintype "output"))
      (node (ref "SV12") (pin "4") (pinfunction "4_4") (pintype "passive"))
    )
    (net (code "50") (name "LED_CH_A_IN") (class "Default")
      (node (ref "IC2") (pin "7") (pinfunction "I7_7") (pintype "input"))
      (node (ref "SV9") (pin "2") (pinfunction "2_2") (pintype "passive"))
    )
    (net (code "51") (name "LED_CH_A_OUT") (class "Default")
      (node (ref "IC2") (pin "10") (pinfunction "O7_10") (pintype "open_collector"))
      (node (ref "LED_A") (pin "K") (pinfunction "C_K") (pintype "passive"))
    )
    (net (code "52") (name "LED_CH_B_IN") (class "Default")
      (node (ref "IC4") (pin "7") (pinfunction "I7_7") (pintype "input"))
      (node (ref "SV9") (pin "5") (pinfunction "5_5") (pintype "passive"))
    )
    (net (code "53") (name "LED_CH_B_OUT") (class "Default")
      (node (ref "IC4") (pin "10") (pinfunction "O7_10") (pintype "open_collector"))
      (node (ref "LED_B") (pin "K") (pinfunction "C_K") (pintype "passive"))
    )
    (net (code "54") (name "LED_CH_C_IN") (class "Default")
      (node (ref "IC5") (pin "7") (pinfunction "I7_7") (pintype "input"))
      (node (ref "SV10") (pin "2") (pinfunction "2_2") (pintype "passive"))
    )
    (net (code "55") (name "LED_CH_C_OUT") (class "Default")
      (node (ref "IC5") (pin "10") (pinfunction "O7_10") (pintype "open_collector"))
      (node (ref "LED_C") (pin "K") (pinfunction "C_K") (pintype "passive"))
    )
    (net (code "56") (name "LED_CH_D_IN") (class "Default")
      (node (ref "IC6") (pin "7") (pinfunction "I7_7") (pintype "input"))
      (node (ref "SV10") (pin "5") (pinfunction "5_5") (pintype "passive"))
    )
    (net (code "57") (name "LED_CH_D_OUT") (class "Default")
      (node (ref "IC6") (pin "10") (pinfunction "O7_10") (pintype "open_collector"))
      (node (ref "LED_D") (pin "K") (pinfunction "C_K") (pintype "passive"))
    )
    (net (code "58") (name "LED_CH_E_IN") (class "Default")
      (node (ref "IC7") (pin "1") (pinfunction "I1_1") (pintype "input"))
      (node (ref "SV11") (pin "2") (pinfunction "2_2") (pintype "passive"))
    )
    (net (code "59") (name "LED_CH_F_IN") (class "Default")
      (node (ref "IC7") (pin "2") (pinfunction "I2_2") (pintype "input"))
      (node (ref "SV11") (pin "5") (pinfunction "5_5") (pintype "passive"))
    )
    (net (code "60") (name "LED_CH_G_IN") (class "Default")
      (node (ref "IC7") (pin "3") (pinfunction "I3_3") (pintype "input"))
      (node (ref "SV12") (pin "2") (pinfunction "2_2") (pintype "passive"))
    )
    (net (code "61") (name "LED_CH_H_IN") (class "Default")
      (node (ref "IC7") (pin "4") (pinfunction "I4_4") (pintype "input"))
      (node (ref "SV12") (pin "5") (pinfunction "5_5") (pintype "passive"))
    )
    (net (code "62") (name "MOTOR_A_FWD") (class "Default")
      (node (ref "IC8") (pin "4") (pinfunction "FIN_4") (pintype "input"))
      (node (ref "SV13") (pin "1") (pinfunction "1_1") (pintype "passive"))
    )
    (net (code "63") (name "MOTOR_A_REV") (class "Default")
      (node (ref "IC8") (pin "5") (pinfunction "RIN_5") (pintype "input"))
      (node (ref "SV13") (pin "2") (pinfunction "2_2") (pintype "passive"))
    )
    (net (code "64") (name "MOTOR_A_VREF") (class "Default")
      (node (ref "IC8") (pin "6") (pinfunction "VREF_6") (pintype "passive"))
      (node (ref "TM9") (pin "2") (pinfunction "S_2") (pintype "passive"))
    )
    (net (code "65") (name "MOTOR_B_FWD") (class "Default")
      (node (ref "IC9") (pin "4") (pinfunction "FIN_4") (pintype "input"))
      (node (ref "SV13") (pin "5") (pinfunction "5_5") (pintype "passive"))
    )
    (net (code "66") (name "MOTOR_B_REV") (class "Default")
      (node (ref "IC9") (pin "5") (pinfunction "RIN_5") (pintype "input"))
      (node (ref "SV13") (pin "6") (pinfunction "6_6") (pintype "passive"))
    )
    (net (code "67") (name "MOTOR_B_VREF") (class "Default")
      (node (ref "IC9") (pin "6") (pinfunction "VREF_6") (pintype "passive"))
      (node (ref "TM10") (pin "2") (pinfunction "S_2") (pintype "passive"))
    )
    (net (code "68") (name "Net-(D13-PadA)") (class "Default")
      (node (ref "D13") (pin "A") (pinfunction "A_A") (pintype "passive"))
      (node (ref "JP8") (pin "1") (pinfunction "1_1") (pintype "passive"))
    )
    (net (code "69") (name "Net-(D13-PadC)") (class "Default")
      (node (ref "D13") (pin "C") (pinfunction "C_C") (pintype "passive"))
      (node (ref "U$7") (pin "COM") (pinfunction "COM_COM") (pintype "bidirectional"))
    )
    (net (code "70") (name "Net-(IC2-O1)") (class "Default")
      (node (ref "D6") (pin "C") (pinfunction "C_C") (pintype "passive"))
      (node (ref "IC2") (pin "16") (pinfunction "O1_16") (pintype "open_collector"))
    )
    (net (code "71") (name "Net-(IC2-O2)") (class "Default")
      (node (ref "D5") (pin "C") (pinfunction "C_C") (pintype "passive"))
      (node (ref "IC2") (pin "15") (pinfunction "O2_15") (pintype "open_collector"))
    )
    (net (code "72") (name "Net-(IC2-O3)") (class "Default")
      (node (ref "D4") (pin "C") (pinfunction "C_C") (pintype "passive"))
      (node (ref "IC2") (pin "14") (pinfunction "O3_14") (pintype "open_collector"))
    )
    (net (code "73") (name "Net-(IC2-O4)") (class "Default")
      (node (ref "D3") (pin "C") (pinfunction "C_C") (pintype "passive"))
      (node (ref "IC2") (pin "13") (pinfunction "O4_13") (pintype "open_collector"))
    )
    (net (code "74") (name "Net-(IC2-O5)") (class "Default")
      (node (ref "D2") (pin "C") (pinfunction "C_C") (pintype "passive"))
      (node (ref "IC2") (pin "12") (pinfunction "O5_12") (pintype "open_collector"))
    )
    (net (code "75") (name "Net-(IC2-O6)") (class "Default")
      (node (ref "D1") (pin "C") (pinfunction "C_C") (pintype "passive"))
      (node (ref "IC2") (pin "11") (pinfunction "O6_11") (pintype "open_collector"))
    )
    (net (code "76") (name "Net-(IC4-O1)") (class "Default")
      (node (ref "D12") (pin "C") (pinfunction "C_C") (pintype "passive"))
      (node (ref "IC4") (pin "16") (pinfunction "O1_16") (pintype "open_collector"))
    )
    (net (code "77") (name "Net-(IC4-O2)") (class "Default")
      (node (ref "D11") (pin "C") (pinfunction "C_C") (pintype "passive"))
      (node (ref "IC4") (pin "15") (pinfunction "O2_15") (pintype "open_collector"))
    )
    (net (code "78") (name "Net-(IC4-O3)") (class "Default")
      (node (ref "D10") (pin "C") (pinfunction "C_C") (pintype "passive"))
      (node (ref "IC4") (pin "14") (pinfunction "O3_14") (pintype "open_collector"))
    )
    (net (code "79") (name "Net-(IC4-O4)") (class "Default")
      (node (ref "D9") (pin "C") (pinfunction "C_C") (pintype "passive"))
      (node (ref "IC4") (pin "13") (pinfunction "O4_13") (pintype "open_collector"))
    )
    (net (code "80") (name "Net-(IC4-O5)") (class "Default")
      (node (ref "D8") (pin "C") (pinfunction "C_C") (pintype "passive"))
      (node (ref "IC4") (pin "12") (pinfunction "O5_12") (pintype "open_collector"))
    )
    (net (code "81") (name "Net-(IC4-O6)") (class "Default")
      (node (ref "D7") (pin "C") (pinfunction "C_C") (pintype "passive"))
      (node (ref "IC4") (pin "11") (pinfunction "O6_11") (pintype "open_collector"))
    )
    (net (code "82") (name "Net-(IC5-O1)") (class "Default")
      (node (ref "D20") (pin "C") (pinfunction "C_C") (pintype "passive"))
      (node (ref "IC5") (pin "16") (pinfunction "O1_16") (pintype "open_collector"))
    )
    (net (code "83") (name "Net-(IC5-O2)") (class "Default")
      (node (ref "D19") (pin "C") (pinfunction "C_C") (pintype "passive"))
      (node (ref "IC5") (pin "15") (pinfunction "O2_15") (pintype "open_collector"))
    )
    (net (code "84") (name "Net-(IC5-O3)") (class "Default")
      (node (ref "D18") (pin "C") (pinfunction "C_C") (pintype "passive"))
      (node (ref "IC5") (pin "14") (pinfunction "O3_14") (pintype "open_collector"))
    )
    (net (code "85") (name "Net-(IC5-O4)") (class "Default")
      (node (ref "D17") (pin "C") (pinfunction "C_C") (pintype "passive"))
      (node (ref "IC5") (pin "13") (pinfunction "O4_13") (pintype "open_collector"))
    )
    (net (code "86") (name "Net-(IC5-O5)") (class "Default")
      (node (ref "D16") (pin "C") (pinfunction "C_C") (pintype "passive"))
      (node (ref "IC5") (pin "12") (pinfunction "O5_12") (pintype "open_collector"))
    )
    (net (code "87") (name "Net-(IC5-O6)") (class "Default")
      (node (ref "D15") (pin "C") (pinfunction "C_C") (pintype "passive"))
      (node (ref "IC5") (pin "11") (pinfunction "O6_11") (pintype "open_collector"))
    )
    (net (code "88") (name "Net-(IC6-O1)") (class "Default")
      (node (ref "D26") (pin "C") (pinfunction "C_C") (pintype "passive"))
      (node (ref "IC6") (pin "16") (pinfunction "O1_16") (pintype "open_collector"))
    )
    (net (code "89") (name "Net-(IC6-O2)") (class "Default")
      (node (ref "D25") (pin "C") (pinfunction "C_C") (pintype "passive"))
      (node (ref "IC6") (pin "15") (pinfunction "O2_15") (pintype "open_collector"))
    )
    (net (code "90") (name "Net-(IC6-O3)") (class "Default")
      (node (ref "D24") (pin "C") (pinfunction "C_C") (pintype "passive"))
      (node (ref "IC6") (pin "14") (pinfunction "O3_14") (pintype "open_collector"))
    )
    (net (code "91") (name "Net-(IC6-O4)") (class "Default")
      (node (ref "D23") (pin "C") (pinfunction "C_C") (pintype "passive"))
      (node (ref "IC6") (pin "13") (pinfunction "O4_13") (pintype "open_collector"))
    )
    (net (code "92") (name "Net-(IC6-O5)") (class "Default")
      (node (ref "D22") (pin "C") (pinfunction "C_C") (pintype "passive"))
      (node (ref "IC6") (pin "12") (pinfunction "O5_12") (pintype "open_collector"))
    )
    (net (code "93") (name "Net-(IC6-O6)") (class "Default")
      (node (ref "D21") (pin "C") (pinfunction "C_C") (pintype "passive"))
      (node (ref "IC6") (pin "11") (pinfunction "O6_11") (pintype "open_collector"))
    )
    (net (code "94") (name "Net-(IC7-O1)") (class "Default")
      (node (ref "IC7") (pin "16") (pinfunction "O1_16") (pintype "open_collector"))
      (node (ref "LED_E") (pin "K") (pinfunction "C_K") (pintype "passive"))
    )
    (net (code "95") (name "Net-(IC7-O2)") (class "Default")
      (node (ref "IC7") (pin "15") (pinfunction "O2_15") (pintype "open_collector"))
      (node (ref "LED_F") (pin "K") (pinfunction "C_K") (pintype "passive"))
    )
    (net (code "96") (name "Net-(IC7-O3)") (class "Default")
      (node (ref "IC7") (pin "14") (pinfunction "O3_14") (pintype "open_collector"))
      (node (ref "LED_G") (pin "K") (pinfunction "C_K") (pintype "passive"))
    )
    (net (code "97") (name "Net-(IC7-O4)") (class "Default")
      (node (ref "IC7") (pin "13") (pinfunction "O4_13") (pintype "open_collector"))
      (node (ref "LED_H") (pin "K") (pinfunction "C_K") (pintype "passive"))
    )
    (net (code "98") (name "Net-(IC8-OUT1)") (class "Default")
      (node (ref "IC8") (pin "1") (pinfunction "OUT1_1") (pintype "output"))
      (node (ref "U$1") (pin "P$2") (pinfunction "P$2_P$2") (pintype "bidirectional"))
    )
    (net (code "99") (name "Net-(IC8-OUT2)") (class "Default")
      (node (ref "IC8") (pin "7") (pinfunction "OUT2_7") (pintype "output"))
      (node (ref "U$1") (pin "P$1") (pinfunction "P$1_P$1") (pintype "bidirectional"))
    )
    (net (code "100") (name "Net-(IC9-OUT1)") (class "Default")
      (node (ref "IC9") (pin "1") (pinfunction "OUT1_1") (pintype "output"))
      (node (ref "U$2") (pin "P$2") (pinfunction "P$2_P$2") (pintype "bidirectional"))
    )
    (net (code "101") (name "Net-(IC9-OUT2)") (class "Default")
      (node (ref "IC9") (pin "7") (pinfunction "OUT2_7") (pintype "output"))
      (node (ref "U$2") (pin "P$1") (pinfunction "P$1_P$1") (pintype "bidirectional"))
    )
    (net (code "102") (name "Net-(LED_A-PadA)") (class "Default")
      (node (ref "LED_A") (pin "A") (pinfunction "A_A") (pintype "passive"))
      (node (ref "U$4") (pin "1") (pinfunction "1_1") (pintype "bidirectional"))
    )
    (net (code "103") (name "Net-(LED_B-PadA)") (class "Default")
      (node (ref "LED_B") (pin "A") (pinfunction "A_A") (pintype "passive"))
      (node (ref "U$4") (pin "2") (pinfunction "2_2") (pintype "bidirectional"))
    )
    (net (code "104") (name "Net-(LED_C-PadA)") (class "Default")
      (node (ref "LED_C") (pin "A") (pinfunction "A_A") (pintype "passive"))
      (node (ref "U$4") (pin "3") (pinfunction "3_3") (pintype "bidirectional"))
    )
    (net (code "105") (name "Net-(LED_D-PadA)") (class "Default")
      (node (ref "LED_D") (pin "A") (pinfunction "A_A") (pintype "passive"))
      (node (ref "U$4") (pin "4") (pinfunction "4_4") (pintype "bidirectional"))
    )
    (net (code "106") (name "Net-(LED_E-PadA)") (class "Default")
      (node (ref "LED_E") (pin "A") (pinfunction "A_A") (pintype "passive"))
      (node (ref "U$4") (pin "6") (pinfunction "6_6") (pintype "bidirectional"))
    )
    (net (code "107") (name "Net-(LED_F-PadA)") (class "Default")
      (node (ref "LED_F") (pin "A") (pinfunction "A_A") (pintype "passive"))
      (node (ref "U$4") (pin "7") (pinfunction "7_7") (pintype "bidirectional"))
    )
    (net (code "108") (name "Net-(LED_G-PadA)") (class "Default")
      (node (ref "LED_G") (pin "A") (pinfunction "A_A") (pintype "passive"))
      (node (ref "U$4") (pin "8") (pinfunction "8_8") (pintype "bidirectional"))
    )
    (net (code "109") (name "Net-(LED_H-PadA)") (class "Default")
      (node (ref "LED_H") (pin "A") (pinfunction "A_A") (pintype "passive"))
      (node (ref "U$4") (pin "9") (pinfunction "9_9") (pintype "bidirectional"))
    )
    (net (code "110") (name "Net-(TM9-E)") (class "Default")
      (node (ref "R8") (pin "2") (pinfunction "2_2") (pintype "passive"))
      (node (ref "TM9") (pin "3") (pinfunction "E_3") (pintype "passive"))
    )
    (net (code "111") (name "Net-(TM10-E)") (class "Default")
      (node (ref "R9") (pin "2") (pinfunction "2_2") (pintype "passive"))
      (node (ref "TM10") (pin "3") (pinfunction "E_3") (pintype "passive"))
    )
    (net (code "112") (name "OUTPUT_A_IN") (class "Default")
      (node (ref "IC7") (pin "6") (pinfunction "I6_6") (pintype "input"))
      (node (ref "SV13") (pin "4") (pinfunction "4_4") (pintype "passive"))
    )
    (net (code "113") (name "OUTPUT_A_OUT") (class "Default")
      (node (ref "IC7") (pin "11") (pinfunction "O6_11") (pintype "open_collector"))
      (node (ref "JP1") (pin "1") (pinfunction "1_1") (pintype "passive"))
    )
    (net (code "114") (name "OUTPUT_B_IN") (class "Default")
      (node (ref "IC7") (pin "5") (pinfunction "I5_5") (pintype "input"))
      (node (ref "SV13") (pin "3") (pinfunction "3_3") (pintype "passive"))
    )
    (net (code "115") (name "OUTPUT_B_OUT") (class "Default")
      (node (ref "IC7") (pin "12") (pinfunction "O5_12") (pintype "open_collector"))
      (node (ref "JP2") (pin "1") (pinfunction "1_1") (pintype "passive"))
    )
    (net (code "116") (name "RES_D1") (class "Default")
      (node (ref "D1") (pin "A") (pinfunction "A_A") (pintype "passive"))
      (node (ref "U$19") (pin "6") (pinfunction "6_6") (pintype "bidirectional"))
    )
    (net (code "117") (name "RES_D2") (class "Default")
      (node (ref "D2") (pin "A") (pinfunction "A_A") (pintype "passive"))
      (node (ref "U$19") (pin "7") (pinfunction "7_7") (pintype "bidirectional"))
    )
    (net (code "118") (name "RES_D3") (class "Default")
      (node (ref "D3") (pin "A") (pinfunction "A_A") (pintype "passive"))
      (node (ref "U$19") (pin "8") (pinfunction "8_8") (pintype "bidirectional"))
    )
    (net (code "119") (name "RES_D4") (class "Default")
      (node (ref "D4") (pin "A") (pinfunction "A_A") (pintype "passive"))
      (node (ref "U$19") (pin "1") (pinfunction "1_1") (pintype "bidirectional"))
    )
    (net (code "120") (name "RES_D5") (class "Default")
      (node (ref "D5") (pin "A") (pinfunction "A_A") (pintype "passive"))
      (node (ref "U$19") (pin "2") (pinfunction "2_2") (pintype "bidirectional"))
    )
    (net (code "121") (name "RES_D6") (class "Default")
      (node (ref "D6") (pin "A") (pinfunction "A_A") (pintype "passive"))
      (node (ref "U$19") (pin "3") (pinfunction "3_3") (pintype "bidirectional"))
    )
    (net (code "122") (name "RES_D7") (class "Default")
      (node (ref "D7") (pin "A") (pinfunction "A_A") (pintype "passive"))
      (node (ref "U$5") (pin "6") (pinfunction "6_6") (pintype "bidirectional"))
    )
    (net (code "123") (name "RES_D8") (class "Default")
      (node (ref "D8") (pin "A") (pinfunction "A_A") (pintype "passive"))
      (node (ref "U$5") (pin "7") (pinfunction "7_7") (pintype "bidirectional"))
    )
    (net (code "124") (name "RES_D9") (class "Default")
      (node (ref "D9") (pin "A") (pinfunction "A_A") (pintype "passive"))
      (node (ref "U$5") (pin "8") (pinfunction "8_8") (pintype "bidirectional"))
    )
    (net (code "125") (name "RES_D10") (class "Default")
      (node (ref "D10") (pin "A") (pinfunction "A_A") (pintype "passive"))
      (node (ref "U$5") (pin "1") (pinfunction "1_1") (pintype "bidirectional"))
    )
    (net (code "126") (name "RES_D11") (class "Default")
      (node (ref "D11") (pin "A") (pinfunction "A_A") (pintype "passive"))
      (node (ref "U$5") (pin "2") (pinfunction "2_2") (pintype "bidirectional"))
    )
    (net (code "127") (name "RES_D12") (class "Default")
      (node (ref "D12") (pin "A") (pinfunction "A_A") (pintype "passive"))
      (node (ref "U$5") (pin "3") (pinfunction "3_3") (pintype "bidirectional"))
    )
    (net (code "128") (name "RES_D15") (class "Default")
      (node (ref "D15") (pin "A") (pinfunction "A_A") (pintype "passive"))
      (node (ref "U$6") (pin "6") (pinfunction "6_6") (pintype "bidirectional"))
    )
    (net (code "129") (name "RES_D16") (class "Default")
      (node (ref "D16") (pin "A") (pinfunction "A_A") (pintype "passive"))
      (node (ref "U$6") (pin "7") (pinfunction "7_7") (pintype "bidirectional"))
    )
    (net (code "130") (name "RES_D17") (class "Default")
      (node (ref "D17") (pin "A") (pinfunction "A_A") (pintype "passive"))
      (node (ref "U$6") (pin "8") (pinfunction "8_8") (pintype "bidirectional"))
    )
    (net (code "131") (name "RES_D18") (class "Default")
      (node (ref "D18") (pin "A") (pinfunction "A_A") (pintype "passive"))
      (node (ref "U$6") (pin "1") (pinfunction "1_1") (pintype "bidirectional"))
    )
    (net (code "132") (name "RES_D19") (class "Default")
      (node (ref "D19") (pin "A") (pinfunction "A_A") (pintype "passive"))
      (node (ref "U$6") (pin "2") (pinfunction "2_2") (pintype "bidirectional"))
    )
    (net (code "133") (name "RES_D20") (class "Default")
      (node (ref "D20") (pin "A") (pinfunction "A_A") (pintype "passive"))
      (node (ref "U$6") (pin "3") (pinfunction "3_3") (pintype "bidirectional"))
    )
    (net (code "134") (name "RES_D21") (class "Default")
      (node (ref "D21") (pin "A") (pinfunction "A_A") (pintype "passive"))
      (node (ref "U$9") (pin "6") (pinfunction "6_6") (pintype "bidirectional"))
    )
    (net (code "135") (name "RES_D22") (class "Default")
      (node (ref "D22") (pin "A") (pinfunction "A_A") (pintype "passive"))
      (node (ref "U$9") (pin "7") (pinfunction "7_7") (pintype "bidirectional"))
    )
    (net (code "136") (name "RES_D23") (class "Default")
      (node (ref "D23") (pin "A") (pinfunction "A_A") (pintype "passive"))
      (node (ref "U$9") (pin "8") (pinfunction "8_8") (pintype "bidirectional"))
    )
    (net (code "137") (name "RES_D24") (class "Default")
      (node (ref "D24") (pin "A") (pinfunction "A_A") (pintype "passive"))
      (node (ref "U$9") (pin "1") (pinfunction "1_1") (pintype "bidirectional"))
    )
    (net (code "138") (name "RES_D25") (class "Default")
      (node (ref "D25") (pin "A") (pinfunction "A_A") (pintype "passive"))
      (node (ref "U$9") (pin "2") (pinfunction "2_2") (pintype "bidirectional"))
    )
    (net (code "139") (name "RES_D26") (class "Default")
      (node (ref "D26") (pin "A") (pinfunction "A_A") (pintype "passive"))
      (node (ref "U$9") (pin "3") (pinfunction "3_3") (pintype "bidirectional"))
    )
    (net (code "140") (name "VDD") (class "Default")
      (node (ref "C2") (pin "2") (pinfunction "2_2") (pintype "passive"))
      (node (ref "C4") (pin "1") (pinfunction "1_1") (pintype "passive"))
      (node (ref "C6") (pin "1") (pinfunction "1_1") (pintype "passive"))
      (node (ref "IC1") (pin "14") (pinfunction "VDD_14") (pintype "power_in"))
      (node (ref "IC10") (pin "2") (pinfunction "VOUT_2") (pintype "output"))
      (node (ref "IC11") (pin "3") (pinfunction "V+_3") (pintype "power_in"))
      (node (ref "IC12") (pin "3") (pinfunction "V+_3") (pintype "power_in"))
      (node (ref "IC2") (pin "9") (pinfunction "CD+_9") (pintype "passive"))
      (node (ref "IC3") (pin "14") (pinfunction "VDD_14") (pintype "power_in"))
      (node (ref "IC4") (pin "9") (pinfunction "CD+_9") (pintype "passive"))
      (node (ref "IC5") (pin "9") (pinfunction "CD+_9") (pintype "passive"))
      (node (ref "IC6") (pin "9") (pinfunction "CD+_9") (pintype "passive"))
      (node (ref "IC7") (pin "9") (pinfunction "CD+_9") (pintype "passive"))
      (node (ref "IC8") (pin "3") (pinfunction "VCC_3") (pintype "power_in"))
      (node (ref "IC9") (pin "3") (pinfunction "VCC_3") (pintype "power_in"))
      (node (ref "JP1") (pin "2") (pinfunction "2_2") (pintype "passive"))
      (node (ref "JP2") (pin "2") (pinfunction "2_2") (pintype "passive"))
      (node (ref "PH1") (pin "1") (pinfunction "1_1") (pintype "passive"))
      (node (ref "PH2") (pin "1") (pinfunction "1_1") (pintype "passive"))
      (node (ref "PH3") (pin "1") (pinfunction "1_1") (pintype "passive"))
      (node (ref "PH4") (pin "1") (pinfunction "1_1") (pintype "passive"))
      (node (ref "PH5") (pin "1") (pinfunction "1_1") (pintype "passive"))
      (node (ref "PH6") (pin "1") (pinfunction "1_1") (pintype "passive"))
      (node (ref "PH7") (pin "1") (pinfunction "1_1") (pintype "passive"))
      (node (ref "PH8") (pin "1") (pinfunction "1_1") (pintype "passive"))
      (node (ref "R8") (pin "1") (pinfunction "1_1") (pintype "passive"))
      (node (ref "R9") (pin "1") (pinfunction "1_1") (pintype "passive"))
      (node (ref "SV10") (pin "1") (pinfunction "1_1") (pintype "passive"))
      (node (ref "SV10") (pin "6") (pinfunction "6_6") (pintype "passive"))
      (node (ref "SV11") (pin "1") (pinfunction "1_1") (pintype "passive"))
      (node (ref "SV11") (pin "6") (pinfunction "6_6") (pintype "passive"))
      (node (ref "SV12") (pin "1") (pinfunction "1_1") (pintype "passive"))
      (node (ref "SV12") (pin "6") (pinfunction "6_6") (pintype "passive"))
      (node (ref "SV14") (pin "4") (pinfunction "4_4") (pintype "passive"))
      (node (ref "SV14") (pin "5") (pinfunction "5_5") (pintype "passive"))
      (node (ref "SV14") (pin "6") (pinfunction "6_6") (pintype "passive"))
      (node (ref "SV15") (pin "4") (pinfunction "4_4") (pintype "passive"))
      (node (ref "SV15") (pin "5") (pinfunction "5_5") (pintype "passive"))
      (node (ref "SV15") (pin "6") (pinfunction "6_6") (pintype "passive"))
      (node (ref "SV9") (pin "1") (pinfunction "1_1") (pintype "passive"))
      (node (ref "SV9") (pin "6") (pinfunction "6_6") (pintype "passive"))
      (node (ref "TM1") (pin "3") (pinfunction "E_3") (pintype "passive"))
      (node (ref "TM2") (pin "3") (pinfunction "E_3") (pintype "passive"))
      (node (ref "TM3") (pin "3") (pinfunction "E_3") (pintype "passive"))
      (node (ref "TM4") (pin "3") (pinfunction "E_3") (pintype "passive"))
      (node (ref "TM5") (pin "3") (pinfunction "E_3") (pintype "passive"))
      (node (ref "TM6") (pin "3") (pinfunction "E_3") (pintype "passive"))
      (node (ref "TM7") (pin "3") (pinfunction "E_3") (pintype "passive"))
      (node (ref "TM8") (pin "3") (pinfunction "E_3") (pintype "passive"))
      (node (ref "U$10") (pin "10") (pinfunction "10_10") (pintype "bidirectional"))
      (node (ref "U$10") (pin "5") (pinfunction "5_5") (pintype "bidirectional"))
      (node (ref "U$11") (pin "10") (pinfunction "10_10") (pintype "bidirectional"))
      (node (ref "U$11") (pin "5") (pinfunction "5_5") (pintype "bidirectional"))
      (node (ref "U$19") (pin "10") (pinfunction "10_10") (pintype "bidirectional"))
      (node (ref "U$19") (pin "5") (pinfunction "5_5") (pintype "bidirectional"))
      (node (ref "U$20") (pin "10") (pinfunction "10_10") (pintype "bidirectional"))
      (node (ref "U$20") (pin "5") (pinfunction "5_5") (pintype "bidirectional"))
      (node (ref "U$3") (pin "10") (pinfunction "10_10") (pintype "bidirectional"))
      (node (ref "U$3") (pin "5") (pinfunction "5_5") (pintype "bidirectional"))
      (node (ref "U$4") (pin "10") (pinfunction "10_10") (pintype "bidirectional"))
      (node (ref "U$4") (pin "5") (pinfunction "5_5") (pintype "bidirectional"))
      (node (ref "U$5") (pin "10") (pinfunction "10_10") (pintype "bidirectional"))
      (node (ref "U$5") (pin "5") (pinfunction "5_5") (pintype "bidirectional"))
      (node (ref "U$6") (pin "10") (pinfunction "10_10") (pintype "bidirectional"))
      (node (ref "U$6") (pin "5") (pinfunction "5_5") (pintype "bidirectional"))
      (node (ref "U$9") (pin "10") (pinfunction "10_10") (pintype "bidirectional"))
      (node (ref "U$9") (pin "5") (pinfunction "5_5") (pintype "bidirectional"))
    )
    (net (code "141") (name "VIN") (class "Default")
      (node (ref "C1") (pin "2") (pinfunction "2_2") (pintype "passive"))
      (node (ref "C3") (pin "1") (pinfunction "1_1") (pintype "passive"))
      (node (ref "C5") (pin "1") (pinfunction "1_1") (pintype "passive"))
      (node (ref "IC10") (pin "3") (pinfunction "VIN_3") (pintype "input"))
      (node (ref "IC8") (pin "2") (pinfunction "VCC_2") (pintype "power_in"))
      (node (ref "IC9") (pin "2") (pinfunction "VCC_2") (pintype "power_in"))
      (node (ref "U$7") (pin "NC") (pinfunction "NC_NC") (pintype "bidirectional"))
    )
    (net (code "142") (name "unconnected-(IC7-I7-Pad7)") (class "Default")
      (node (ref "IC7") (pin "7") (pinfunction "I7_7") (pintype "input"))
    )
    (net (code "143") (name "unconnected-(IC7-O7-Pad10)") (class "Default")
      (node (ref "IC7") (pin "10") (pinfunction "O7_10") (pintype "open_collector"))
    )
    (net (code "144") (name "unconnected-(U$3-Pad4)") (class "Default")
      (node (ref "U$3") (pin "4") (pinfunction "4_4") (pintype "bidirectional"))
    )
    (net (code "145") (name "unconnected-(U$3-Pad9)") (class "Default")
      (node (ref "U$3") (pin "9") (pinfunction "9_9") (pintype "bidirectional"))
    )
    (net (code "146") (name "unconnected-(U$5-Pad4)") (class "Default")
      (node (ref "U$5") (pin "4") (pinfunction "4_4") (pintype "bidirectional"))
    )
    (net (code "147") (name "unconnected-(U$5-Pad9)") (class "Default")
      (node (ref "U$5") (pin "9") (pinfunction "9_9") (pintype "bidirectional"))
    )
    (net (code "148") (name "unconnected-(U$6-Pad4)") (class "Default")
      (node (ref "U$6") (pin "4") (pinfunction "4_4") (pintype "bidirectional"))
    )
    (net (code "149") (name "unconnected-(U$6-Pad9)") (class "Default")
      (node (ref "U$6") (pin "9") (pinfunction "9_9") (pintype "bidirectional"))
    )
    (net (code "150") (name "unconnected-(U$7-PadNO)") (class "Default")
      (node (ref "U$7") (pin "NO") (pinfunction "NO_NO") (pintype "bidirectional"))
    )
    (net (code "151") (name "unconnected-(U$9-Pad4)") (class "Default")
      (node (ref "U$9") (pin "4") (pinfunction "4_4") (pintype "bidirectional"))
    )
    (net (code "152") (name "unconnected-(U$9-Pad9)") (class "Default")
      (node (ref "U$9") (pin "9") (pinfunction "9_9") (pintype "bidirectional"))
    )
    (net (code "153") (name "unconnected-(U$10-Pad4)") (class "Default")
      (node (ref "U$10") (pin "4") (pinfunction "4_4") (pintype "bidirectional"))
    )
    (net (code "154") (name "unconnected-(U$10-Pad9)") (class "Default")
      (node (ref "U$10") (pin "9") (pinfunction "9_9") (pintype "bidirectional"))
    )
    (net (code "155") (name "unconnected-(U$11-Pad4)") (class "Default")
      (node (ref "U$11") (pin "4") (pinfunction "4_4") (pintype "bidirectional"))
    )
    (net (code "156") (name "unconnected-(U$11-Pad9)") (class "Default")
      (node (ref "U$11") (pin "9") (pinfunction "9_9") (pintype "bidirectional"))
    )
    (net (code "157") (name "unconnected-(U$19-Pad4)") (class "Default")
      (node (ref "U$19") (pin "4") (pinfunction "4_4") (pintype "bidirectional"))
    )
    (net (code "158") (name "unconnected-(U$19-Pad9)") (class "Default")
      (node (ref "U$19") (pin "9") (pinfunction "9_9") (pintype "bidirectional"))
    )
    (net (code "159") (name "unconnected-(U$20-Pad4)") (class "Default")
      (node (ref "U$20") (pin "4") (pinfunction "4_4") (pintype "bidirectional"))
    )
    (net (code "160") (name "unconnected-(U$20-Pad9)") (class "Default")
      (node (ref "U$20") (pin "9") (pinfunction "9_9") (pintype "bidirectional"))
    )
  )
)
